# 105358-3SC001-02_BlockDiagram.net
KiCad netlist of a schematic drawn in Altium Designer
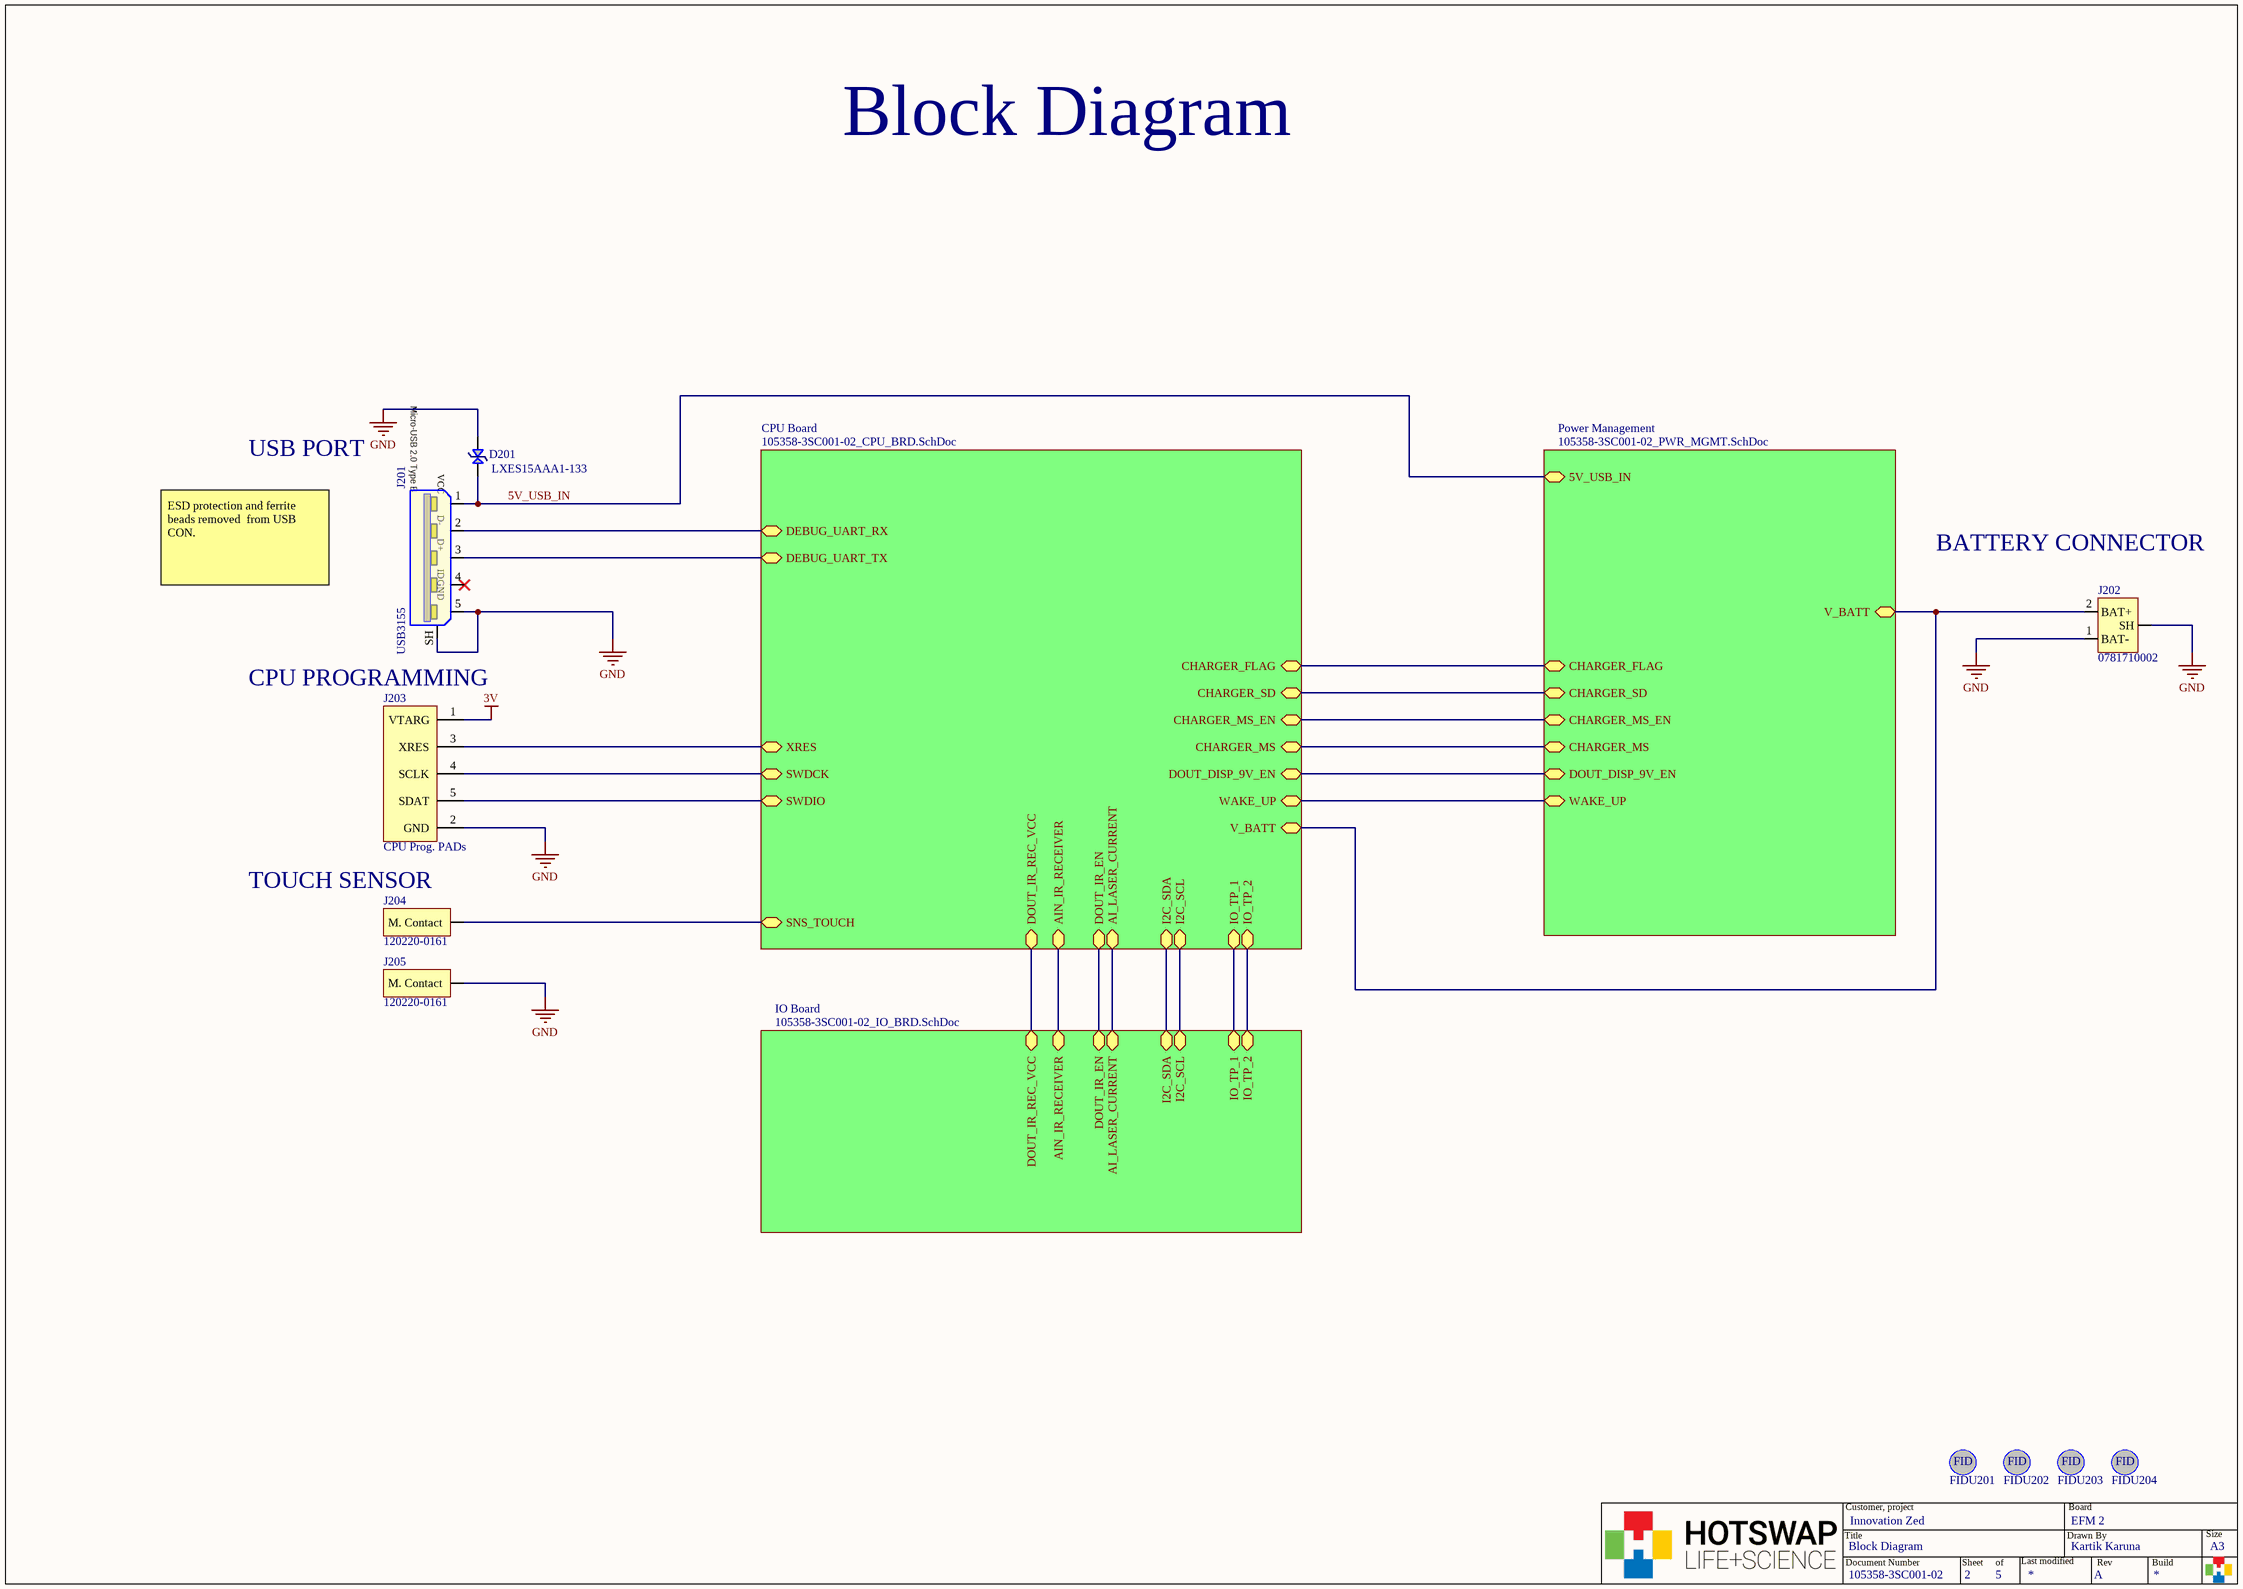
[diagram p0: 105358-3SC001-02_BlockDiagram.SchDoc]

(export (version "E")
  (design (tool "Eeschema 10.0.6"))
  (components
    (comp (ref "D201")
      (value "LXES15AAA1-133")
      (footprint "0402C-GENERIC")
      (description "TVS DIODE 15VWM 0402")
      (fields
        (field (name "MANUFACTURER") "Murata Electronics North America")
        (field (name "DIGI-KEY PART NUMBER") "490-13209-1-ND")
      )
      (libsource (lib "ConnectMedical") (part "TVS DIODE 15VWM 0402"))
    )
    (comp (ref "FIDU201")
      (value "FIDU-miniROUND")
      (footprint "FIDU-MINI-ROUND")
      (libsource (lib "ConnectMedical") (part "FIDU-miniROUND"))
    )
    (comp (ref "FIDU202")
      (value "FIDU-miniROUND")
      (footprint "FIDU-MINI-ROUND")
      (libsource (lib "ConnectMedical") (part "FIDU-miniROUND"))
    )
    (comp (ref "FIDU203")
      (value "FIDU-miniROUND")
      (footprint "FIDU-MINI-ROUND")
      (libsource (lib "ConnectMedical") (part "FIDU-miniROUND"))
    )
    (comp (ref "FIDU204")
      (value "FIDU-miniROUND")
      (footprint "FIDU-MINI-ROUND")
      (libsource (lib "ConnectMedical") (part "FIDU-miniROUND"))
    )
    (comp (ref "J201")
      (value "USB3155")
      (footprint "USB3155")
      (description "CONN RCPT USB-mini B 2.0 5POS SLD")
      (fields
        (field (name "MANUFACTURER") "GCT (GLOBAL CONNECTOR TECHNOLOGY)")
        (field (name "MANUFACTURER PART NUMBER") "USB3155-30-A")
      )
      (libsource (lib "ConnectMedical") (part "USB3155"))
    )
    (comp (ref "J202")
      (value "0781710002")
      (footprint "PAD 0781710002")
      (description "1.20MM WTB HEADER VERT 2POS")
      (fields (field (name "MANUFACTURER") "Molex, LLC") (field (name "DIGI-KEY PART NUMBER") "WM4459CT-ND"))
      (libsource (lib "ConnectMedical") (part "CONNECTOR 1.20MM WTB HEADER VERT 2POS"))
    )
    (comp (ref "J203")
      (value "CPU Prog. PADs")
      (footprint "PAD PROGRAMMING")
      (description "CPU Programming PADs")
      (libsource (lib "ConnectMedical") (part "PROGRAMMING PADS"))
    )
    (comp (ref "J204")
      (value "120220-0161")
      (footprint "PAD 1.0x3.76mm")
      (description "UNIVERSAL CONTACT 2.5MM SMD")
      (fields
        (field (name "MANUFACTURER") "ITT Cannon, LLC")
        (field (name "DIGI-KEY PART NUMBER") "1003-1009-1-ND")
      )
      (libsource (lib "ConnectMedical") (part "UNIVERSAL_CONTACT_2.5MM SMD"))
    )
    (comp (ref "J205")
      (value "120220-0161")
      (footprint "PAD 1.0x3.76mm")
      (description "UNIVERSAL CONTACT 2.5MM SMD")
      (fields
        (field (name "MANUFACTURER") "ITT Cannon, LLC")
        (field (name "DIGI-KEY PART NUMBER") "1003-1009-1-ND")
      )
      (libsource (lib "ConnectMedical") (part "UNIVERSAL_CONTACT_2.5MM SMD"))
    )
  )
  (nets
    (net (code "1") (name "/5V_USB_IN") (class "Default")
      (node (ref "D201") (pin "2") (pinfunction "2_2") (pintype "passive"))
      (node (ref "J201") (pin "1") (pinfunction "VCC_1") (pintype "passive"))
    )
    (net (code "8") (name "/DEBUG_UART_RX") (class "Default")
      (node (ref "J201") (pin "2") (pinfunction "D-_2") (pintype "passive"))
    )
    (net (code "9") (name "/DEBUG_UART_TX") (class "Default")
      (node (ref "J201") (pin "3") (pinfunction "D+_3") (pintype "passive"))
    )
    (net (code "17") (name "/SNS_TOUCH") (class "Default")
      (node (ref "J204") (pin "1") (pinfunction "M._Contact_1") (pintype "passive"))
    )
    (net (code "18") (name "/SWDCK") (class "Default")
      (node (ref "J203") (pin "4") (pinfunction "SCLK_4") (pintype "passive"))
    )
    (net (code "19") (name "/SWDIO") (class "Default")
      (node (ref "J203") (pin "5") (pinfunction "SDAT_5") (pintype "passive"))
    )
    (net (code "20") (name "/V_BATT") (class "Default")
      (node (ref "J202") (pin "2") (pinfunction "BAT+_2") (pintype "passive"))
    )
    (net (code "22") (name "/XRES") (class "Default")
      (node (ref "J203") (pin "3") (pinfunction "XRES_3") (pintype "passive"))
    )
    (net (code "23") (name "3V") (class "Default")
      (node (ref "J203") (pin "1") (pinfunction "VTARG_1") (pintype "passive"))
    )
    (net (code "24") (name "GND") (class "Default")
      (node (ref "D201") (pin "1") (pinfunction "1_1") (pintype "passive"))
      (node (ref "J201") (pin "5") (pinfunction "GND_5") (pintype "passive"))
      (node (ref "J201") (pin "SH") (pinfunction "Shell_SH") (pintype "passive"))
      (node (ref "J202") (pin "1") (pinfunction "BAT-_1") (pintype "passive"))
      (node (ref "J202") (pin "3") (pinfunction "SH_3") (pintype "passive"))
      (node (ref "J203") (pin "2") (pinfunction "GND_2") (pintype "passive"))
      (node (ref "J205") (pin "1") (pinfunction "M._Contact_1") (pintype "passive"))
    )
    (net (code "25") (name "unconnected-(J201-ID-Pad4)") (class "Default")
      (node (ref "J201") (pin "4") (pinfunction "ID_4") (pintype "passive+no_connect"))
    )
  )
)
